# power5V12V.net
KiCad netlist of a schematic drawn in EAGLE
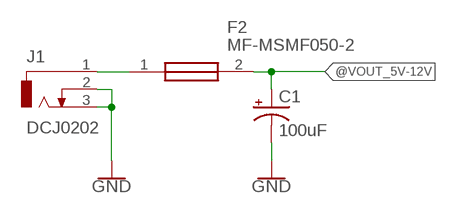
[diagram p0: schematic, sheet 1]

(export (version "E")
  (design (tool "Eeschema 10.0.6"))
  (components
    (comp (ref "C1")
      (value "100uF")
      (footprint "eagle-import:EIA7343")
      (libsource (lib "eagle-import") (part "100UF-POLAR-EIA7343-10V-10%(TANT)"))
    )
    (comp (ref "F2")
      (value "MF-MSMF050-2")
      (footprint "eagle-import:FUSC4632X85N")
      (fields (field (name "MOUSER_PART_NUMBER") "652-MF-MSMF050-2"))
      (libsource (lib "eagle-import") (part "MF-MSMF050-2"))
    )
    (comp (ref "J1")
      (value "DCJ0202")
      (footprint "eagle-import:DCJ0202")
      (libsource (lib "eagle-import") (part "DCJ0202"))
    )
  )
  (nets
    (net (code "1") (name "@VOUT_5V-12V") (class "Default")
      (node (ref "C1") (pin "A") (pinfunction "+_A") (pintype "passive"))
      (node (ref "F2") (pin "2") (pinfunction "2_2") (pintype "bidirectional"))
    )
    (net (code "2") (name "GND") (class "Default")
      (node (ref "C1") (pin "C") (pinfunction "-_C") (pintype "passive"))
      (node (ref "J1") (pin "2") (pinfunction "2_2") (pintype "passive"))
      (node (ref "J1") (pin "3") (pinfunction "3_3") (pintype "passive"))
    )
    (net (code "3") (name "Net-(F2-Pad1)") (class "Default")
      (node (ref "F2") (pin "1") (pinfunction "1_1") (pintype "bidirectional"))
      (node (ref "J1") (pin "1") (pinfunction "1_1") (pintype "passive"))
    )
  )
)
